# ESP32-C3-WROOM-2.net
KiCad netlist of a schematic drawn in Altium Designer
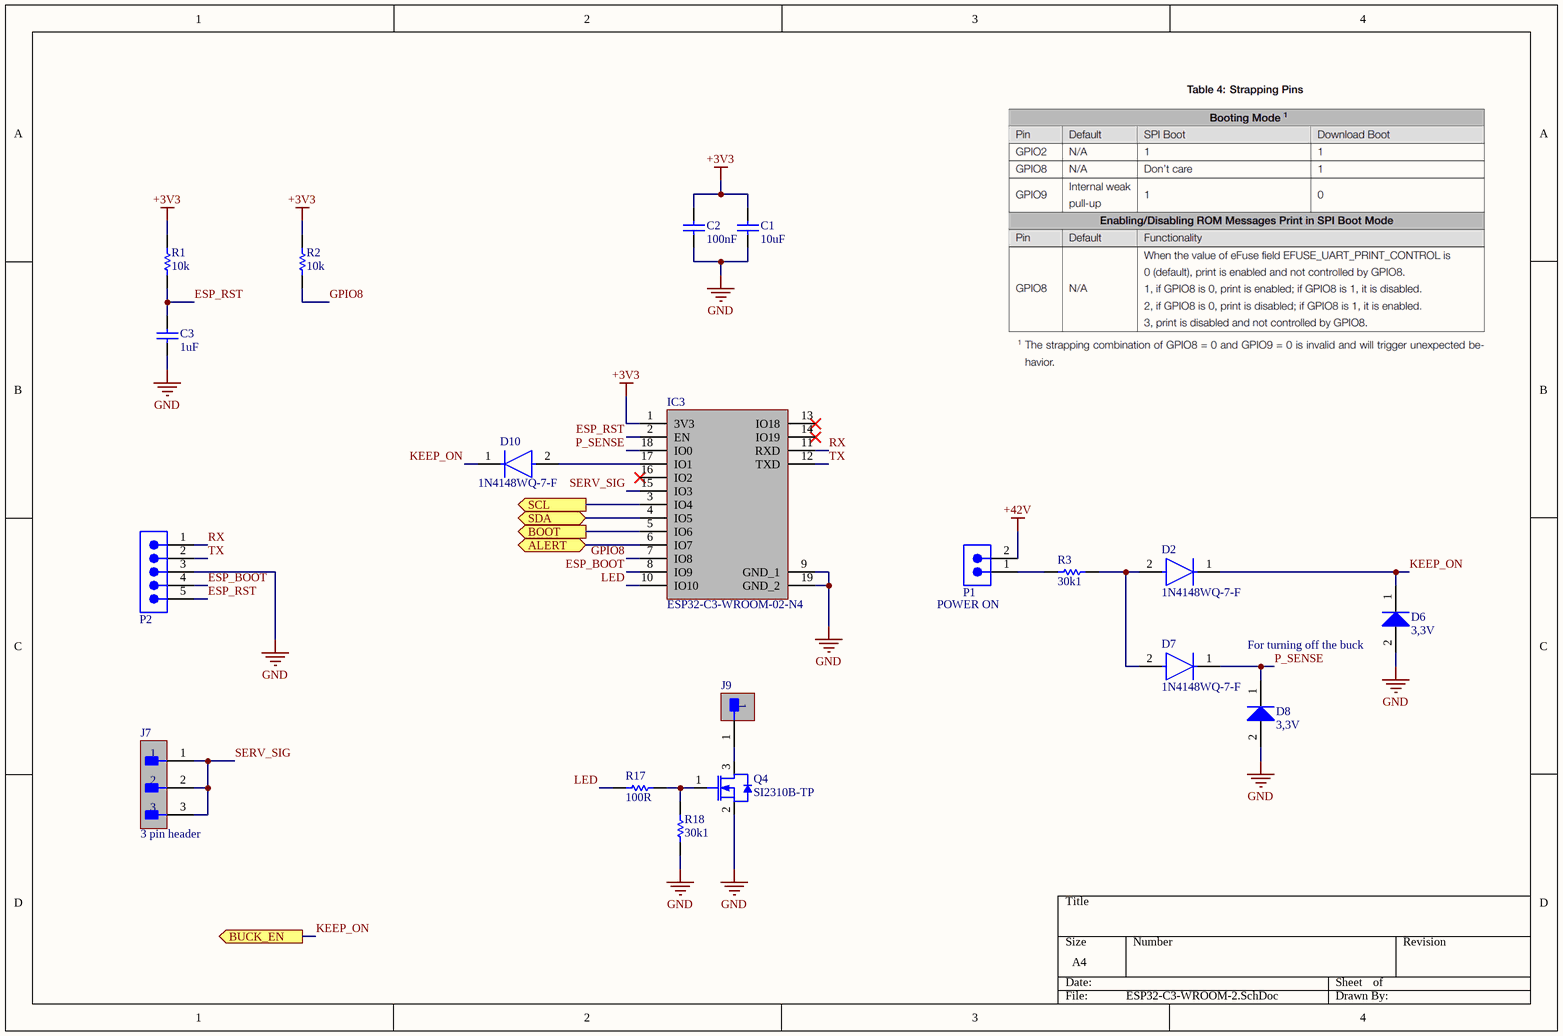
[diagram p0: ESP32-C3-WROOM-2.SchDoc]

(export (version "E")
  (design (tool "Eeschema 10.0.6"))
  (components
    (comp (ref "C1")
      (value "10uF")
      (footprint "Wurth 0603 capacitor")
      (fields (field (name "Comment") "Generic Capacitor 10uF 0603"))
      (libsource (lib "Passives") (part "Generic Capacitor 10uF 0603"))
    )
    (comp (ref "C2")
      (value "100nF")
      (footprint "Wurth 0603 capacitor")
      (fields (field (name "Comment") "Generic Capacitor 100nF 0603"))
      (libsource (lib "Passives") (part "Generic Capacitor 100nF 0603"))
    )
    (comp (ref "C3")
      (value "1uF")
      (footprint "Wurth 0603 capacitor")
      (fields (field (name "Comment") "Generic Capacitor 1uF 0603"))
      (libsource (lib "Passives") (part "Generic Capacitor 1uF 0603"))
    )
    (comp (ref "D2")
      (value "1N4148WQ-7-F")
      (footprint "FP-SOD123-MFG")
      (description "DIODE GEN PURP 100V 300MA SOD123")
      (fields
        (field (name "MANUFACTURER") "Diodes Inc.")
        (field (name "OCTOPART") "https://octopart.com/1n4148wq-7-f-diodes+inc.-34965875")
      )
      (libsource (lib "Altium Content Vault") (part "d7152d700b627762746794eb795d46e"))
    )
    (comp (ref "D6")
      (value "3,3V")
      (footprint "SOD-123")
      (fields (field (name "Comment") "BZT52C3V3"))
      (libsource (lib "Passives") (part "GOODWORK BZT52C3V3"))
    )
    (comp (ref "D7")
      (value "1N4148WQ-7-F")
      (footprint "FP-SOD123-MFG")
      (description "DIODE GEN PURP 100V 300MA SOD123")
      (fields
        (field (name "MANUFACTURER") "Diodes Inc.")
        (field (name "OCTOPART") "https://octopart.com/1n4148wq-7-f-diodes+inc.-34965875")
      )
      (libsource (lib "Altium Content Vault") (part "d7152d700b627762746794eb795d46e"))
    )
    (comp (ref "D8")
      (value "3,3V")
      (footprint "SOD-123")
      (fields (field (name "Comment") "BZT52C3V3"))
      (libsource (lib "Passives") (part "GOODWORK BZT52C3V3"))
    )
    (comp (ref "D10")
      (value "1N4148WQ-7-F")
      (footprint "FP-SOD123-MFG")
      (description "DIODE GEN PURP 100V 300MA SOD123")
      (fields
        (field (name "MANUFACTURER") "Diodes Inc.")
        (field (name "OCTOPART") "https://octopart.com/1n4148wq-7-f-diodes+inc.-34965875")
      )
      (libsource (lib "Altium Content Vault") (part "d7152d700b627762746794eb795d46e"))
    )
    (comp (ref "IC3")
      (value "ESP32-C3-WROOM-02-N4")
      (footprint "Espressif ESP32C3WROOM02N4")
      (description "Integrated Circuit")
      (fields (field (name "MOUSER PART NUMBER") "356-ESP32C3WROOM02N4"))
      (libsource (lib "MCU's") (part "Espressif ESP32-C3-WROOM-02-N4"))
    )
    (comp (ref "J7")
      (value "3 pin header")
      (footprint "3 pin header 2.54mm")
      (libsource (lib "Headers") (part "3 pin header"))
    )
    (comp (ref "J9")
      (value "1 pin header")
      (footprint "1 pin header")
      (libsource (lib "Headers") (part "1 pin header"))
    )
    (comp (ref "P1")
      (value "POWER ON")
      (footprint "2x1 2.54mm M")
      (description "WR-PHD Pin Header, THT, Vertical, pitch 2.54mm, 1 Row, 2P")
      (fields
        (field (name "MANUFACTURER PART NUMBER") "61300211121")
        (field (name "MANUFACTURER") "Wurth Elektronik")
      )
      (libsource (lib "2.54mm_pin_headers") (part "2P"))
    )
    (comp (ref "P2")
      (value "61300511121")
      (footprint "5x1 2.54mm")
      (description "WR-PHD Pin Header, THT, Vertical, pitch 2.54mm, 1 Row, 5P")
      (fields (field (name "MANUFACTURER") "Wurth Elektronik"))
      (libsource (lib "2.54mm_pin_headers") (part "5P"))
    )
    (comp (ref "Q4")
      (value "SI2310B-TP")
      (footprint "MCC SOT-23-3")
      (description "Power Field-Effect Transistor")
      (fields (field (name "MANUFACTURER") "MCC"))
      (libsource (lib "N CHN FET") (part "MCC SI2310B-TP"))
    )
    (comp (ref "R1")
      (value "10k")
      (footprint "Wurth 0603 Resistor")
      (fields (field (name "Comment") "Generic Resistor 10k 0603"))
      (libsource (lib "Passives") (part "Generic Resistor 10k 0603"))
    )
    (comp (ref "R2")
      (value "10k")
      (footprint "Wurth 0603 Resistor")
      (fields (field (name "Comment") "Generic Resistor 10k 0603"))
      (libsource (lib "Passives") (part "Generic Resistor 10k 0603"))
    )
    (comp (ref "R3")
      (value "30k1")
      (footprint "Wurth 0603 Resistor")
      (fields (field (name "Comment") "Generic Resistor 30k1 0603"))
      (libsource (lib "Passives") (part "Generic Resistor 30k1 0603"))
    )
    (comp (ref "R17")
      (value "100R")
      (footprint "Wurth 0603 Resistor")
      (fields (field (name "Comment") "Generic Resistor 100R 0603"))
      (libsource (lib "Passives") (part "Generic Resistor 100R 0603"))
    )
    (comp (ref "R18")
      (value "30k1")
      (footprint "Wurth 0603 Resistor")
      (fields (field (name "Comment") "Generic Resistor 30k1 0603"))
      (libsource (lib "Passives") (part "Generic Resistor 30k1 0603"))
    )
  )
  (nets
    (net (code "1") (name "+3V3") (class "Default")
      (node (ref "C1") (pin "2") (pinfunction "2_2") (pintype "passive"))
      (node (ref "C2") (pin "2") (pinfunction "2_2") (pintype "passive"))
      (node (ref "IC3") (pin "1") (pinfunction "3V3_1") (pintype "passive"))
      (node (ref "R1") (pin "2") (pinfunction "2_2") (pintype "passive"))
      (node (ref "R2") (pin "2") (pinfunction "2_2") (pintype "passive"))
    )
    (net (code "2") (name "+42V") (class "Default")
      (node (ref "P1") (pin "2") (pinfunction "2_2") (pintype "passive"))
    )
    (net (code "3") (name "/ALERT") (class "Default")
      (node (ref "IC3") (pin "6") (pinfunction "IO7_6") (pintype "passive"))
    )
    (net (code "4") (name "/BOOT") (class "Default")
      (node (ref "IC3") (pin "5") (pinfunction "IO6_5") (pintype "passive"))
    )
    (net (code "5") (name "/ESP_BOOT") (class "Default")
      (node (ref "IC3") (pin "8") (pinfunction "IO9_8") (pintype "passive"))
      (node (ref "P2") (pin "4") (pinfunction "4_4") (pintype "passive"))
    )
    (net (code "6") (name "/ESP_RST") (class "Default")
      (node (ref "C3") (pin "2") (pinfunction "2_2") (pintype "passive"))
      (node (ref "IC3") (pin "2") (pinfunction "EN_2") (pintype "passive"))
      (node (ref "P2") (pin "5") (pinfunction "5_5") (pintype "passive"))
      (node (ref "R1") (pin "1") (pinfunction "1_1") (pintype "passive"))
    )
    (net (code "7") (name "/GPIO8") (class "Default")
      (node (ref "IC3") (pin "7") (pinfunction "IO8_7") (pintype "passive"))
      (node (ref "R2") (pin "1") (pinfunction "1_1") (pintype "passive"))
    )
    (net (code "8") (name "/KEEP_ON") (class "Default")
      (node (ref "D10") (pin "1") (pinfunction "C_1") (pintype "passive"))
      (node (ref "D2") (pin "1") (pinfunction "C_1") (pintype "passive"))
      (node (ref "D6") (pin "1") (pinfunction "K_1") (pintype "passive"))
    )
    (net (code "9") (name "/LED") (class "Default")
      (node (ref "IC3") (pin "10") (pinfunction "IO10_10") (pintype "passive"))
      (node (ref "R17") (pin "1") (pinfunction "1_1") (pintype "passive"))
    )
    (net (code "10") (name "/P_SENSE") (class "Default")
      (node (ref "D7") (pin "1") (pinfunction "C_1") (pintype "passive"))
      (node (ref "D8") (pin "1") (pinfunction "K_1") (pintype "passive"))
      (node (ref "IC3") (pin "18") (pinfunction "IO0_18") (pintype "passive"))
    )
    (net (code "11") (name "/RX") (class "Default")
      (node (ref "IC3") (pin "11") (pinfunction "RXD_11") (pintype "passive"))
      (node (ref "P2") (pin "1") (pinfunction "1_1") (pintype "passive"))
    )
    (net (code "12") (name "/SCL") (class "Default")
      (node (ref "IC3") (pin "3") (pinfunction "IO4_3") (pintype "passive"))
    )
    (net (code "13") (name "/SDA") (class "Default")
      (node (ref "IC3") (pin "4") (pinfunction "IO5_4") (pintype "passive"))
    )
    (net (code "14") (name "/SERV_SIG") (class "Default")
      (node (ref "IC3") (pin "15") (pinfunction "IO3_15") (pintype "passive"))
      (node (ref "J7") (pin "1") (pinfunction "1_1") (pintype "passive"))
      (node (ref "J7") (pin "2") (pinfunction "2_2") (pintype "passive"))
      (node (ref "J7") (pin "3") (pinfunction "3_3") (pintype "passive"))
    )
    (net (code "15") (name "/TX") (class "Default")
      (node (ref "IC3") (pin "12") (pinfunction "TXD_12") (pintype "passive"))
      (node (ref "P2") (pin "2") (pinfunction "2_2") (pintype "passive"))
    )
    (net (code "16") (name "GND") (class "Default")
      (node (ref "C1") (pin "1") (pinfunction "1_1") (pintype "passive"))
      (node (ref "C2") (pin "1") (pinfunction "1_1") (pintype "passive"))
      (node (ref "C3") (pin "1") (pinfunction "1_1") (pintype "passive"))
      (node (ref "D6") (pin "2") (pinfunction "A_2") (pintype "passive"))
      (node (ref "D8") (pin "2") (pinfunction "A_2") (pintype "passive"))
      (node (ref "IC3") (pin "19") (pinfunction "GND_2_19") (pintype "passive"))
      (node (ref "IC3") (pin "9") (pinfunction "GND_1_9") (pintype "passive"))
      (node (ref "P2") (pin "3") (pinfunction "3_3") (pintype "passive"))
      (node (ref "Q4") (pin "2") (pinfunction "S_2") (pintype "passive"))
      (node (ref "R18") (pin "1") (pinfunction "1_1") (pintype "passive"))
    )
    (net (code "17") (name "Net-(D2-A)") (class "Default")
      (node (ref "D2") (pin "2") (pinfunction "A_2") (pintype "passive"))
      (node (ref "D7") (pin "2") (pinfunction "A_2") (pintype "passive"))
      (node (ref "R3") (pin "2") (pinfunction "2_2") (pintype "passive"))
    )
    (net (code "18") (name "Net-(D10-A)") (class "Default")
      (node (ref "D10") (pin "2") (pinfunction "A_2") (pintype "passive"))
      (node (ref "IC3") (pin "17") (pinfunction "IO1_17") (pintype "passive"))
    )
    (net (code "19") (name "Net-(P1-Pad1)") (class "Default")
      (node (ref "P1") (pin "1") (pinfunction "1_1") (pintype "passive"))
      (node (ref "R3") (pin "1") (pinfunction "1_1") (pintype "passive"))
    )
    (net (code "20") (name "Net-(Q4-D)") (class "Default")
      (node (ref "J9") (pin "1") (pinfunction "1_1") (pintype "passive"))
      (node (ref "Q4") (pin "3") (pinfunction "D_3") (pintype "passive"))
    )
    (net (code "21") (name "Net-(Q4-G)") (class "Default")
      (node (ref "Q4") (pin "1") (pinfunction "G_1") (pintype "passive"))
      (node (ref "R17") (pin "2") (pinfunction "2_2") (pintype "passive"))
      (node (ref "R18") (pin "2") (pinfunction "2_2") (pintype "passive"))
    )
    (net (code "22") (name "unconnected-(IC3-IO2-Pad16)") (class "Default")
      (node (ref "IC3") (pin "16") (pinfunction "IO2_16") (pintype "passive+no_connect"))
    )
    (net (code "23") (name "unconnected-(IC3-IO18-Pad13)") (class "Default")
      (node (ref "IC3") (pin "13") (pinfunction "IO18_13") (pintype "passive+no_connect"))
    )
    (net (code "24") (name "unconnected-(IC3-IO19-Pad14)") (class "Default")
      (node (ref "IC3") (pin "14") (pinfunction "IO19_14") (pintype "passive+no_connect"))
    )
  )
)
